# floyd.net
KiCad netlist of a schematic drawn in EAGLE
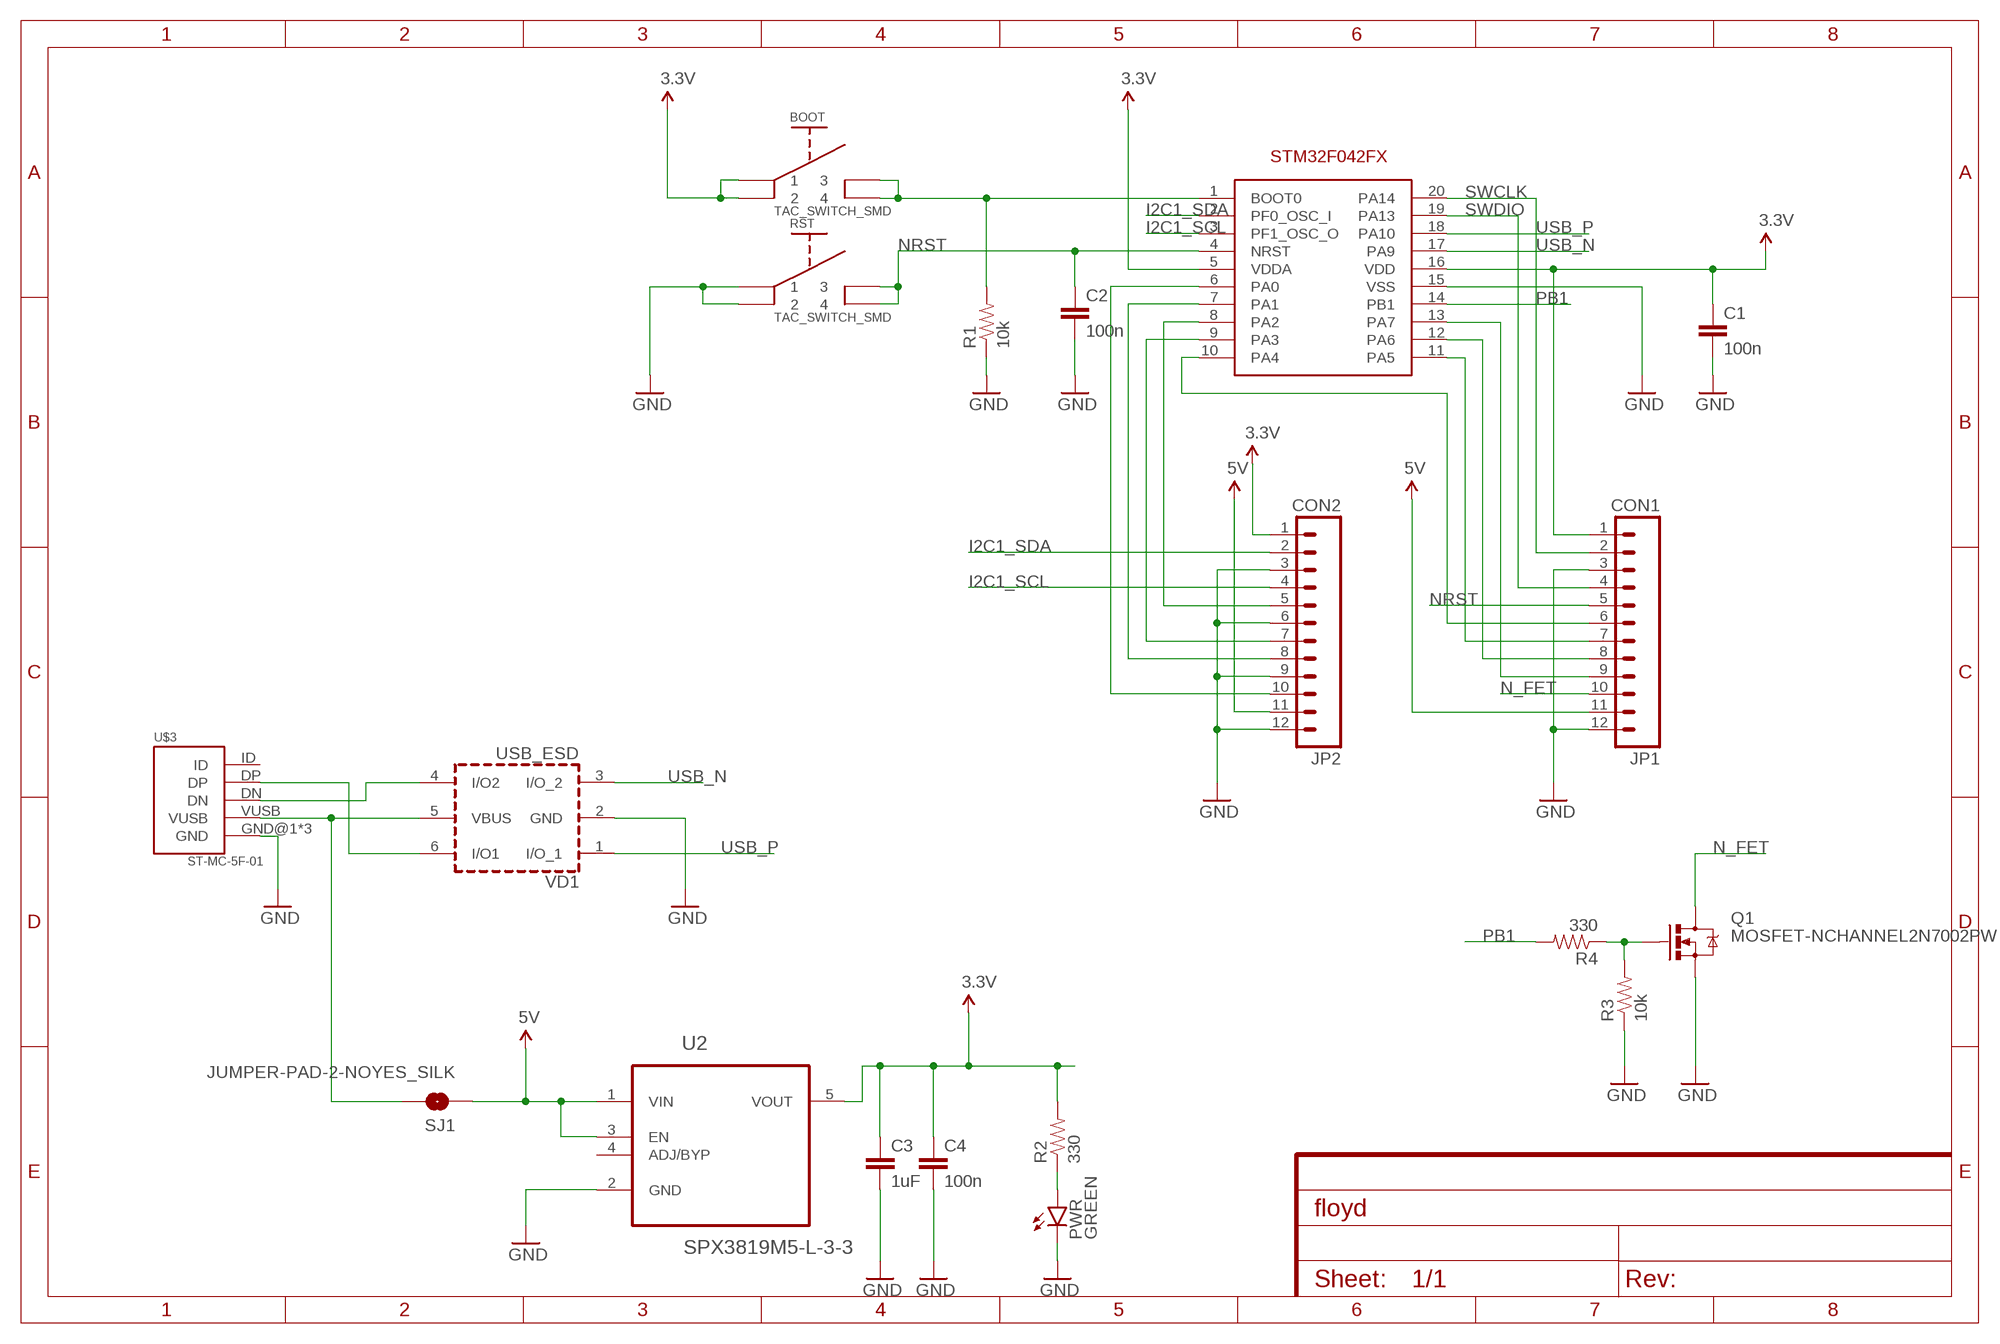
[diagram p0: schematic, sheet 1]

(export (version "E")
  (design (tool "Eeschema 10.0.6"))
  (components
    (comp (ref "BOOT")
      (value "TS-017A")
      (footprint "eagle-import:TS-017ASMD")
      (libsource (lib "eagle-import") (part "TS-017A"))
    )
    (comp (ref "C1")
      (value "100n")
      (footprint "eagle-import:0603-CAP")
      (libsource (lib "eagle-import") (part "CAP0603-CAP"))
    )
    (comp (ref "C2")
      (value "100n")
      (footprint "eagle-import:0603-CAP")
      (libsource (lib "eagle-import") (part "CAP0603-CAP"))
    )
    (comp (ref "C3")
      (value "1uF")
      (footprint "eagle-import:0603-CAP")
      (libsource (lib "eagle-import") (part "CAP0603-CAP"))
    )
    (comp (ref "C4")
      (value "100n")
      (footprint "eagle-import:0603-CAP")
      (libsource (lib "eagle-import") (part "CAP0603-CAP"))
    )
    (comp (ref "JP1")
      (value "CON1")
      (footprint "eagle-import:1X12_LOCK_LONGPADS")
      (libsource (lib "eagle-import") (part "M12LOCK_LONGPADS"))
    )
    (comp (ref "JP2")
      (value "CON2")
      (footprint "eagle-import:1X12_LOCK_LONGPADS")
      (libsource (lib "eagle-import") (part "M12LOCK_LONGPADS"))
    )
    (comp (ref "PWR")
      (value "GREEN")
      (footprint "eagle-import:LED-0603")
      (libsource (lib "eagle-import") (part "LED0603"))
    )
    (comp (ref "Q1")
      (value "MOSFET-NCHANNEL2N7002PW")
      (footprint "eagle-import:SOT323")
      (libsource (lib "eagle-import") (part "MOSFET-NCHANNEL2N7002PW"))
    )
    (comp (ref "R1")
      (value "10k")
      (footprint "eagle-import:0603-RES")
      (libsource (lib "eagle-import") (part "RESISTOR0603-RES"))
    )
    (comp (ref "R2")
      (value "330")
      (footprint "eagle-import:0603-RES")
      (libsource (lib "eagle-import") (part "RESISTOR0603-RES"))
    )
    (comp (ref "R3")
      (value "10k")
      (footprint "eagle-import:0603-RES")
      (libsource (lib "eagle-import") (part "RESISTOR0603-RES"))
    )
    (comp (ref "R4")
      (value "330")
      (footprint "eagle-import:0603-RES")
      (libsource (lib "eagle-import") (part "RESISTOR0603-RES"))
    )
    (comp (ref "RST")
      (value "TS-017A")
      (footprint "eagle-import:TS-017ASMD")
      (libsource (lib "eagle-import") (part "TS-017A"))
    )
    (comp (ref "SJ1")
      (value "JUMPER-PAD-2-NOYES_SILK")
      (footprint "eagle-import:PAD-JUMPER-2-NO_YES_SILK")
      (libsource (lib "eagle-import") (part "JUMPER-PAD-2-NOYES_SILK"))
    )
    (comp (ref "U$3")
      (value "ST-MC-5F-01")
      (footprint "eagle-import:ST-MC-5F-01")
      (libsource (lib "eagle-import") (part "ST-MC-5F-01"))
    )
    (comp (ref "U1")
      (value "STM32F042FX")
      (footprint "eagle-import:TSSOP20")
      (libsource (lib "eagle-import") (part "STM32F042FX"))
    )
    (comp (ref "U2")
      (value "SPX3819M5-L-3-3")
      (footprint "eagle-import:SOT95P280X145-5N")
      (libsource (lib "eagle-import") (part "SPX3819M5-L-3-3"))
    )
    (comp (ref "VD1")
      (value "USB_ESD")
      (footprint "eagle-import:SOT-23-6L")
      (libsource (lib "eagle-import") (part "USBLC6-2SC6"))
    )
  )
  (nets
    (net (code "1") (name "/I2C1_SCL") (class "Default")
      (node (ref "JP2") (pin "4") (pinfunction "4_4") (pintype "passive"))
      (node (ref "U1") (pin "3") (pinfunction "PF1_OSC_O_3") (pintype "bidirectional"))
    )
    (net (code "2") (name "/I2C1_SDA") (class "Default")
      (node (ref "JP2") (pin "2") (pinfunction "2_2") (pintype "passive"))
      (node (ref "U1") (pin "2") (pinfunction "PF0_OSC_I_2") (pintype "bidirectional"))
    )
    (net (code "3") (name "/NRST") (class "Default")
      (node (ref "C2") (pin "1") (pinfunction "1_1") (pintype "passive"))
      (node (ref "JP1") (pin "5") (pinfunction "5_5") (pintype "passive"))
      (node (ref "RST") (pin "P$3") (pinfunction "3_P$3") (pintype "bidirectional"))
      (node (ref "RST") (pin "P$4") (pinfunction "4_P$4") (pintype "bidirectional"))
      (node (ref "U1") (pin "4") (pinfunction "NRST_4") (pintype "input"))
    )
    (net (code "4") (name "/N_FET") (class "Default")
      (node (ref "JP1") (pin "10") (pinfunction "10_10") (pintype "passive"))
      (node (ref "Q1") (pin "3") (pinfunction "D_3") (pintype "passive"))
    )
    (net (code "5") (name "/PB1") (class "Default")
      (node (ref "R4") (pin "2") (pinfunction "2_2") (pintype "passive"))
      (node (ref "U1") (pin "14") (pinfunction "PB1_14") (pintype "bidirectional"))
    )
    (net (code "6") (name "/SWCLK") (class "Default")
      (node (ref "JP1") (pin "2") (pinfunction "2_2") (pintype "passive"))
      (node (ref "U1") (pin "20") (pinfunction "PA14_20") (pintype "bidirectional"))
    )
    (net (code "7") (name "/SWDIO") (class "Default")
      (node (ref "JP1") (pin "4") (pinfunction "4_4") (pintype "passive"))
      (node (ref "U1") (pin "19") (pinfunction "PA13_19") (pintype "bidirectional"))
    )
    (net (code "8") (name "/USB_N") (class "Default")
      (node (ref "U1") (pin "17") (pinfunction "PA9_17") (pintype "bidirectional"))
      (node (ref "VD1") (pin "3") (pinfunction "I/O_2_3") (pintype "bidirectional"))
    )
    (net (code "9") (name "/USB_P") (class "Default")
      (node (ref "U1") (pin "18") (pinfunction "PA10_18") (pintype "bidirectional"))
      (node (ref "VD1") (pin "1") (pinfunction "I/O_1_1") (pintype "bidirectional"))
    )
    (net (code "10") (name "3.3V") (class "Default")
      (node (ref "BOOT") (pin "P$1") (pinfunction "1_P$1") (pintype "bidirectional"))
      (node (ref "BOOT") (pin "P$2") (pinfunction "2_P$2") (pintype "bidirectional"))
      (node (ref "C1") (pin "1") (pinfunction "1_1") (pintype "passive"))
      (node (ref "C3") (pin "1") (pinfunction "1_1") (pintype "passive"))
      (node (ref "C4") (pin "1") (pinfunction "1_1") (pintype "passive"))
      (node (ref "JP1") (pin "1") (pinfunction "1_1") (pintype "passive"))
      (node (ref "JP2") (pin "1") (pinfunction "1_1") (pintype "passive"))
      (node (ref "R2") (pin "2") (pinfunction "2_2") (pintype "passive"))
      (node (ref "U1") (pin "16") (pinfunction "VDD_16") (pintype "power_in"))
      (node (ref "U1") (pin "5") (pinfunction "VDDA_5") (pintype "power_in"))
      (node (ref "U2") (pin "5") (pinfunction "VOUT_5") (pintype "output"))
    )
    (net (code "11") (name "5V") (class "Default")
      (node (ref "JP1") (pin "11") (pinfunction "11_11") (pintype "passive"))
      (node (ref "JP2") (pin "11") (pinfunction "11_11") (pintype "passive"))
      (node (ref "SJ1") (pin "1") (pinfunction "1_1") (pintype "passive"))
      (node (ref "U2") (pin "1") (pinfunction "VIN_1") (pintype "power_in"))
      (node (ref "U2") (pin "3") (pinfunction "EN_3") (pintype "input"))
    )
    (net (code "12") (name "GND") (class "Default")
      (node (ref "C1") (pin "2") (pinfunction "2_2") (pintype "passive"))
      (node (ref "C2") (pin "2") (pinfunction "2_2") (pintype "passive"))
      (node (ref "C3") (pin "2") (pinfunction "2_2") (pintype "passive"))
      (node (ref "C4") (pin "2") (pinfunction "2_2") (pintype "passive"))
      (node (ref "JP1") (pin "12") (pinfunction "12_12") (pintype "passive"))
      (node (ref "JP1") (pin "3") (pinfunction "3_3") (pintype "passive"))
      (node (ref "JP2") (pin "12") (pinfunction "12_12") (pintype "passive"))
      (node (ref "JP2") (pin "3") (pinfunction "3_3") (pintype "passive"))
      (node (ref "JP2") (pin "6") (pinfunction "6_6") (pintype "passive"))
      (node (ref "JP2") (pin "9") (pinfunction "9_9") (pintype "passive"))
      (node (ref "PWR") (pin "C") (pinfunction "C_C") (pintype "passive"))
      (node (ref "Q1") (pin "2") (pinfunction "S_2") (pintype "passive"))
      (node (ref "R1") (pin "1") (pinfunction "1_1") (pintype "passive"))
      (node (ref "R3") (pin "1") (pinfunction "1_1") (pintype "passive"))
      (node (ref "RST") (pin "P$1") (pinfunction "1_P$1") (pintype "bidirectional"))
      (node (ref "RST") (pin "P$2") (pinfunction "2_P$2") (pintype "bidirectional"))
      (node (ref "U$3") (pin "GND@1") (pinfunction "GND_GND@1") (pintype "power_in"))
      (node (ref "U$3") (pin "GND@2") (pinfunction "GND_GND@2") (pintype "power_in"))
      (node (ref "U$3") (pin "GND@3") (pinfunction "GND_GND@3") (pintype "power_in"))
      (node (ref "U1") (pin "15") (pinfunction "VSS_15") (pintype "power_in"))
      (node (ref "U2") (pin "2") (pinfunction "GND_2") (pintype "passive"))
      (node (ref "VD1") (pin "2") (pinfunction "GND_2") (pintype "bidirectional"))
    )
    (net (code "13") (name "Net-(BOOT-3)") (class "Default")
      (node (ref "BOOT") (pin "P$3") (pinfunction "3_P$3") (pintype "bidirectional"))
      (node (ref "BOOT") (pin "P$4") (pinfunction "4_P$4") (pintype "bidirectional"))
      (node (ref "R1") (pin "2") (pinfunction "2_2") (pintype "passive"))
      (node (ref "U1") (pin "1") (pinfunction "BOOT0_1") (pintype "bidirectional"))
    )
    (net (code "14") (name "Net-(PWR-PadA)") (class "Default")
      (node (ref "PWR") (pin "A") (pinfunction "A_A") (pintype "passive"))
      (node (ref "R2") (pin "1") (pinfunction "1_1") (pintype "passive"))
    )
    (net (code "15") (name "Net-(Q1-G)") (class "Default")
      (node (ref "Q1") (pin "1") (pinfunction "G_1") (pintype "passive"))
      (node (ref "R3") (pin "2") (pinfunction "2_2") (pintype "passive"))
      (node (ref "R4") (pin "1") (pinfunction "1_1") (pintype "passive"))
    )
    (net (code "16") (name "Net-(U1-PA0)") (class "Default")
      (node (ref "JP2") (pin "10") (pinfunction "10_10") (pintype "passive"))
      (node (ref "U1") (pin "6") (pinfunction "PA0_6") (pintype "bidirectional"))
    )
    (net (code "17") (name "Net-(U1-PA1)") (class "Default")
      (node (ref "JP2") (pin "8") (pinfunction "8_8") (pintype "passive"))
      (node (ref "U1") (pin "7") (pinfunction "PA1_7") (pintype "bidirectional"))
    )
    (net (code "18") (name "Net-(U1-PA2)") (class "Default")
      (node (ref "JP2") (pin "5") (pinfunction "5_5") (pintype "passive"))
      (node (ref "U1") (pin "8") (pinfunction "PA2_8") (pintype "bidirectional"))
    )
    (net (code "19") (name "Net-(U1-PA3)") (class "Default")
      (node (ref "JP2") (pin "7") (pinfunction "7_7") (pintype "passive"))
      (node (ref "U1") (pin "9") (pinfunction "PA3_9") (pintype "bidirectional"))
    )
    (net (code "20") (name "Net-(U1-PA4)") (class "Default")
      (node (ref "JP1") (pin "6") (pinfunction "6_6") (pintype "passive"))
      (node (ref "U1") (pin "10") (pinfunction "PA4_10") (pintype "bidirectional"))
    )
    (net (code "21") (name "Net-(U1-PA5)") (class "Default")
      (node (ref "JP1") (pin "7") (pinfunction "7_7") (pintype "passive"))
      (node (ref "U1") (pin "11") (pinfunction "PA5_11") (pintype "bidirectional"))
    )
    (net (code "22") (name "Net-(U1-PA6)") (class "Default")
      (node (ref "JP1") (pin "8") (pinfunction "8_8") (pintype "passive"))
      (node (ref "U1") (pin "12") (pinfunction "PA6_12") (pintype "bidirectional"))
    )
    (net (code "23") (name "Net-(U1-PA7)") (class "Default")
      (node (ref "JP1") (pin "9") (pinfunction "9_9") (pintype "passive"))
      (node (ref "U1") (pin "13") (pinfunction "PA7_13") (pintype "bidirectional"))
    )
    (net (code "24") (name "Net-(VD1-I{slash}O1)") (class "Default")
      (node (ref "U$3") (pin "DP") (pinfunction "DP_DP") (pintype "bidirectional"))
      (node (ref "VD1") (pin "6") (pinfunction "I/O1_6") (pintype "bidirectional"))
    )
    (net (code "25") (name "Net-(VD1-I{slash}O2)") (class "Default")
      (node (ref "U$3") (pin "DN") (pinfunction "DN_DN") (pintype "bidirectional"))
      (node (ref "VD1") (pin "4") (pinfunction "I/O2_4") (pintype "bidirectional"))
    )
    (net (code "26") (name "Net-(VD1-VBUS)") (class "Default")
      (node (ref "SJ1") (pin "2") (pinfunction "2_2") (pintype "passive"))
      (node (ref "U$3") (pin "VUSB") (pinfunction "VUSB_VUSB") (pintype "bidirectional"))
      (node (ref "VD1") (pin "5") (pinfunction "VBUS_5") (pintype "bidirectional"))
    )
    (net (code "27") (name "unconnected-(U$3-PadID)") (class "Default")
      (node (ref "U$3") (pin "ID") (pinfunction "ID_ID") (pintype "bidirectional"))
    )
    (net (code "28") (name "unconnected-(U2-ADJ{slash}BYP-Pad4)") (class "Default")
      (node (ref "U2") (pin "4") (pinfunction "ADJ/BYP_4") (pintype "passive"))
    )
  )
)
